# BANK3.net
KiCad netlist of a schematic drawn in Altium Designer
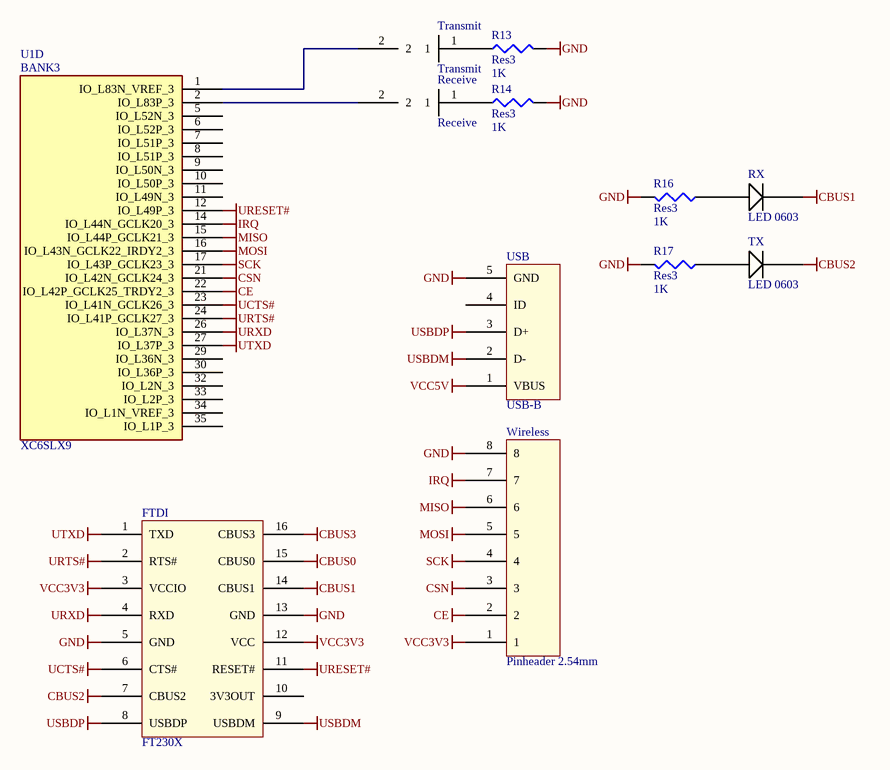
[diagram p0: BANK3.SchDoc]

(export (version "E")
  (design (tool "Eeschema 10.0.6"))
  (components
    (comp (ref "FTDI")
      (value "FT230X")
      (footprint "FT230X")
      (libsource (lib "Mainboard_component_schematics") (part "FT230X"))
    )
    (comp (ref "R13")
      (value "Res3")
      (footprint "J1-0603")
      (description "Resistor")
      (fields (field (name "ALTIUM_VALUE") "1K") (field (name "PUBLISHER") "Altium Limited"))
      (libsource (lib "Miscellaneous Devices") (part "Res3"))
    )
    (comp (ref "R14")
      (value "Res3")
      (footprint "J1-0603")
      (description "Resistor")
      (fields (field (name "ALTIUM_VALUE") "1K") (field (name "PUBLISHER") "Altium Limited"))
      (libsource (lib "Miscellaneous Devices") (part "Res3"))
    )
    (comp (ref "R16")
      (value "Res3")
      (footprint "J1-0603")
      (description "Resistor")
      (fields (field (name "ALTIUM_VALUE") "1K") (field (name "PUBLISHER") "Altium Limited"))
      (libsource (lib "Miscellaneous Devices") (part "Res3"))
    )
    (comp (ref "R17")
      (value "Res3")
      (footprint "J1-0603")
      (description "Resistor")
      (fields (field (name "ALTIUM_VALUE") "1K") (field (name "PUBLISHER") "Altium Limited"))
      (libsource (lib "Miscellaneous Devices") (part "Res3"))
    )
    (comp (ref "Receive") (value "Receive") (footprint "LED") (libsource (lib "") (part "LED 0603_1")))
    (comp (ref "RX")
      (value "LED 0603")
      (footprint "LED")
      (libsource (lib "Mainboard_component_schematics") (part "LED 0603"))
    )
    (comp (ref "Transmit") (value "Transmit") (footprint "LED") (libsource (lib "") (part "LED 0603_1")))
    (comp (ref "TX")
      (value "LED 0603")
      (footprint "LED")
      (libsource (lib "Mainboard_component_schematics") (part "LED 0603"))
    )
    (comp (ref "U1")
      (value "XC6SLX9")
      (footprint "XC6SLX9")
      (description "Imported")
      (libsource (lib "Mainboard_component_schematics") (part "C6SLX9"))
    )
    (comp (ref "USB")
      (value "USB-B")
      (footprint "USB-B mini")
      (libsource (lib "Mainboard_component_schematics") (part "USB-B"))
    )
    (comp (ref "Wireless")
      (value "Pinheader 2.54mm")
      (footprint "Pinheader 2.54mm")
      (libsource (lib "Mainboard_component_schematics") (part "Pinheader 2.54mm"))
    )
  )
  (nets
    (net (code "1") (name "CBUS0") (class "Default")
      (node (ref "FTDI") (pin "15") (pinfunction "CBUS0_15") (pintype "passive"))
    )
    (net (code "2") (name "CBUS1") (class "Default")
      (node (ref "FTDI") (pin "14") (pinfunction "CBUS1_14") (pintype "passive"))
      (node (ref "RX") (pin "2") (pinfunction "2_2") (pintype "passive"))
    )
    (net (code "3") (name "CBUS2") (class "Default")
      (node (ref "FTDI") (pin "7") (pinfunction "CBUS2_7") (pintype "passive"))
      (node (ref "TX") (pin "2") (pinfunction "2_2") (pintype "passive"))
    )
    (net (code "4") (name "CBUS3") (class "Default")
      (node (ref "FTDI") (pin "16") (pinfunction "CBUS3_16") (pintype "passive"))
    )
    (net (code "5") (name "CE") (class "Default")
      (node (ref "U1") (pin "22") (pinfunction "IO_L42P_GCLK25_TRDY2_3_22") (pintype "passive"))
      (node (ref "Wireless") (pin "2") (pinfunction "2_2") (pintype "passive"))
    )
    (net (code "6") (name "CSN") (class "Default")
      (node (ref "U1") (pin "21") (pinfunction "IO_L42N_GCLK24_3_21") (pintype "passive"))
      (node (ref "Wireless") (pin "3") (pinfunction "3_3") (pintype "passive"))
    )
    (net (code "7") (name "GND") (class "Default")
      (node (ref "FTDI") (pin "13") (pinfunction "GND_13") (pintype "passive"))
      (node (ref "FTDI") (pin "5") (pinfunction "GND_5") (pintype "passive"))
      (node (ref "R13") (pin "2") (pinfunction "2_2") (pintype "passive"))
      (node (ref "R14") (pin "2") (pinfunction "2_2") (pintype "passive"))
      (node (ref "R16") (pin "2") (pinfunction "2_2") (pintype "passive"))
      (node (ref "R17") (pin "2") (pinfunction "2_2") (pintype "passive"))
      (node (ref "USB") (pin "5") (pinfunction "GND_5") (pintype "passive"))
      (node (ref "Wireless") (pin "8") (pinfunction "8_8") (pintype "passive"))
    )
    (net (code "8") (name "IRQ") (class "Default")
      (node (ref "U1") (pin "14") (pinfunction "IO_L44N_GCLK20_3_14") (pintype "passive"))
      (node (ref "Wireless") (pin "7") (pinfunction "7_7") (pintype "passive"))
    )
    (net (code "9") (name "MISO") (class "Default")
      (node (ref "U1") (pin "15") (pinfunction "IO_L44P_GCLK21_3_15") (pintype "passive"))
      (node (ref "Wireless") (pin "6") (pinfunction "6_6") (pintype "passive"))
    )
    (net (code "10") (name "MOSI") (class "Default")
      (node (ref "U1") (pin "16") (pinfunction "IO_L43N_GCLK22_IRDY2_3_16") (pintype "passive"))
      (node (ref "Wireless") (pin "5") (pinfunction "5_5") (pintype "passive"))
    )
    (net (code "11") (name "Net-(R13-Pad1)") (class "Default")
      (node (ref "R13") (pin "1") (pinfunction "1_1") (pintype "passive"))
      (node (ref "Transmit") (pin "1") (pinfunction "1_1") (pintype "passive"))
    )
    (net (code "12") (name "Net-(R14-Pad1)") (class "Default")
      (node (ref "R14") (pin "1") (pinfunction "1_1") (pintype "passive"))
      (node (ref "Receive") (pin "1") (pinfunction "1_1") (pintype "passive"))
    )
    (net (code "13") (name "Net-(R16-Pad1)") (class "Default")
      (node (ref "R16") (pin "1") (pinfunction "1_1") (pintype "passive"))
      (node (ref "RX") (pin "1") (pinfunction "1_1") (pintype "passive"))
    )
    (net (code "14") (name "Net-(R17-Pad1)") (class "Default")
      (node (ref "R17") (pin "1") (pinfunction "1_1") (pintype "passive"))
      (node (ref "TX") (pin "1") (pinfunction "1_1") (pintype "passive"))
    )
    (net (code "15") (name "Net-(U1D-IO_L83N_VREF_3)") (class "Default")
      (node (ref "Transmit") (pin "2") (pinfunction "2_2") (pintype "passive"))
      (node (ref "U1") (pin "1") (pinfunction "IO_L83N_VREF_3_1") (pintype "passive"))
    )
    (net (code "16") (name "Net-(U1D-IO_L83P_3)") (class "Default")
      (node (ref "Receive") (pin "2") (pinfunction "2_2") (pintype "passive"))
      (node (ref "U1") (pin "2") (pinfunction "IO_L83P_3_2") (pintype "passive"))
    )
    (net (code "17") (name "SCK") (class "Default")
      (node (ref "U1") (pin "17") (pinfunction "IO_L43P_GCLK23_3_17") (pintype "passive"))
      (node (ref "Wireless") (pin "4") (pinfunction "4_4") (pintype "passive"))
    )
    (net (code "18") (name "UCTS#") (class "Default")
      (node (ref "FTDI") (pin "6") (pinfunction "CTS#_6") (pintype "passive"))
      (node (ref "U1") (pin "23") (pinfunction "IO_L41N_GCLK26_3_23") (pintype "passive"))
    )
    (net (code "19") (name "URESET#") (class "Default")
      (node (ref "FTDI") (pin "11") (pinfunction "RESET#_11") (pintype "passive"))
      (node (ref "U1") (pin "12") (pinfunction "IO_L49P_3_12") (pintype "passive"))
    )
    (net (code "20") (name "URTS#") (class "Default")
      (node (ref "FTDI") (pin "2") (pinfunction "RTS#_2") (pintype "passive"))
      (node (ref "U1") (pin "24") (pinfunction "IO_L41P_GCLK27_3_24") (pintype "passive"))
    )
    (net (code "21") (name "URXD") (class "Default")
      (node (ref "FTDI") (pin "4") (pinfunction "RXD_4") (pintype "passive"))
      (node (ref "U1") (pin "26") (pinfunction "IO_L37N_3_26") (pintype "passive"))
    )
    (net (code "22") (name "USBDM") (class "Default")
      (node (ref "FTDI") (pin "9") (pinfunction "USBDM_9") (pintype "passive"))
      (node (ref "USB") (pin "2") (pinfunction "D-_2") (pintype "passive"))
    )
    (net (code "23") (name "USBDP") (class "Default")
      (node (ref "FTDI") (pin "8") (pinfunction "USBDP_8") (pintype "passive"))
      (node (ref "USB") (pin "3") (pinfunction "D+_3") (pintype "passive"))
    )
    (net (code "24") (name "UTXD") (class "Default")
      (node (ref "FTDI") (pin "1") (pinfunction "TXD_1") (pintype "passive"))
      (node (ref "U1") (pin "27") (pinfunction "IO_L37P_3_27") (pintype "passive"))
    )
    (net (code "25") (name "VCC3V3") (class "Default")
      (node (ref "FTDI") (pin "12") (pinfunction "VCC_12") (pintype "passive"))
      (node (ref "FTDI") (pin "3") (pinfunction "VCCIO_3") (pintype "passive"))
      (node (ref "Wireless") (pin "1") (pinfunction "1_1") (pintype "passive"))
    )
    (net (code "26") (name "VCC5V") (class "Default")
      (node (ref "USB") (pin "1") (pinfunction "VBUS_1") (pintype "passive"))
    )
    (net (code "27") (name "unconnected-(FTDI-3V3OUT-Pad10)") (class "Default")
      (node (ref "FTDI") (pin "10") (pinfunction "3V3OUT_10") (pintype "passive"))
    )
    (net (code "28") (name "unconnected-(U1D-IO_L1N_VREF_3-Pad34)") (class "Default")
      (node (ref "U1") (pin "34") (pinfunction "IO_L1N_VREF_3_34") (pintype "passive"))
    )
    (net (code "29") (name "unconnected-(U1D-IO_L1P_3-Pad35)") (class "Default")
      (node (ref "U1") (pin "35") (pinfunction "IO_L1P_3_35") (pintype "passive"))
    )
    (net (code "30") (name "unconnected-(U1D-IO_L2N_3-Pad32)") (class "Default")
      (node (ref "U1") (pin "32") (pinfunction "IO_L2N_3_32") (pintype "passive"))
    )
    (net (code "31") (name "unconnected-(U1D-IO_L2P_3-Pad33)") (class "Default")
      (node (ref "U1") (pin "33") (pinfunction "IO_L2P_3_33") (pintype "passive"))
    )
    (net (code "32") (name "unconnected-(U1D-IO_L36N_3-Pad29)") (class "Default")
      (node (ref "U1") (pin "29") (pinfunction "IO_L36N_3_29") (pintype "passive"))
    )
    (net (code "33") (name "unconnected-(U1D-IO_L36P_3-Pad30)") (class "Default")
      (node (ref "U1") (pin "30") (pinfunction "IO_L36P_3_30") (pintype "passive"))
    )
    (net (code "34") (name "unconnected-(U1D-IO_L49N_3-Pad11)") (class "Default")
      (node (ref "U1") (pin "11") (pinfunction "IO_L49N_3_11") (pintype "passive"))
    )
    (net (code "35") (name "unconnected-(U1D-IO_L50N_3-Pad9)") (class "Default")
      (node (ref "U1") (pin "9") (pinfunction "IO_L50N_3_9") (pintype "passive"))
    )
    (net (code "36") (name "unconnected-(U1D-IO_L50P_3-Pad10)") (class "Default")
      (node (ref "U1") (pin "10") (pinfunction "IO_L50P_3_10") (pintype "passive"))
    )
    (net (code "37") (name "unconnected-(U1D-IO_L51P_3-Pad7)") (class "Default")
      (node (ref "U1") (pin "7") (pinfunction "IO_L51P_3_7") (pintype "passive"))
    )
    (net (code "38") (name "unconnected-(U1D-IO_L51P_3-Pad8)") (class "Default")
      (node (ref "U1") (pin "8") (pinfunction "IO_L51P_3_8") (pintype "passive"))
    )
    (net (code "39") (name "unconnected-(U1D-IO_L52N_3-Pad5)") (class "Default")
      (node (ref "U1") (pin "5") (pinfunction "IO_L52N_3_5") (pintype "passive"))
    )
    (net (code "40") (name "unconnected-(U1D-IO_L52P_3-Pad6)") (class "Default")
      (node (ref "U1") (pin "6") (pinfunction "IO_L52P_3_6") (pintype "passive"))
    )
    (net (code "41") (name "unconnected-(USB-ID-Pad4)") (class "Default")
      (node (ref "USB") (pin "4") (pinfunction "ID_4") (pintype "passive"))
    )
  )
)
